# deltabot-heater-bed.net
KiCad netlist of a schematic drawn in EAGLE
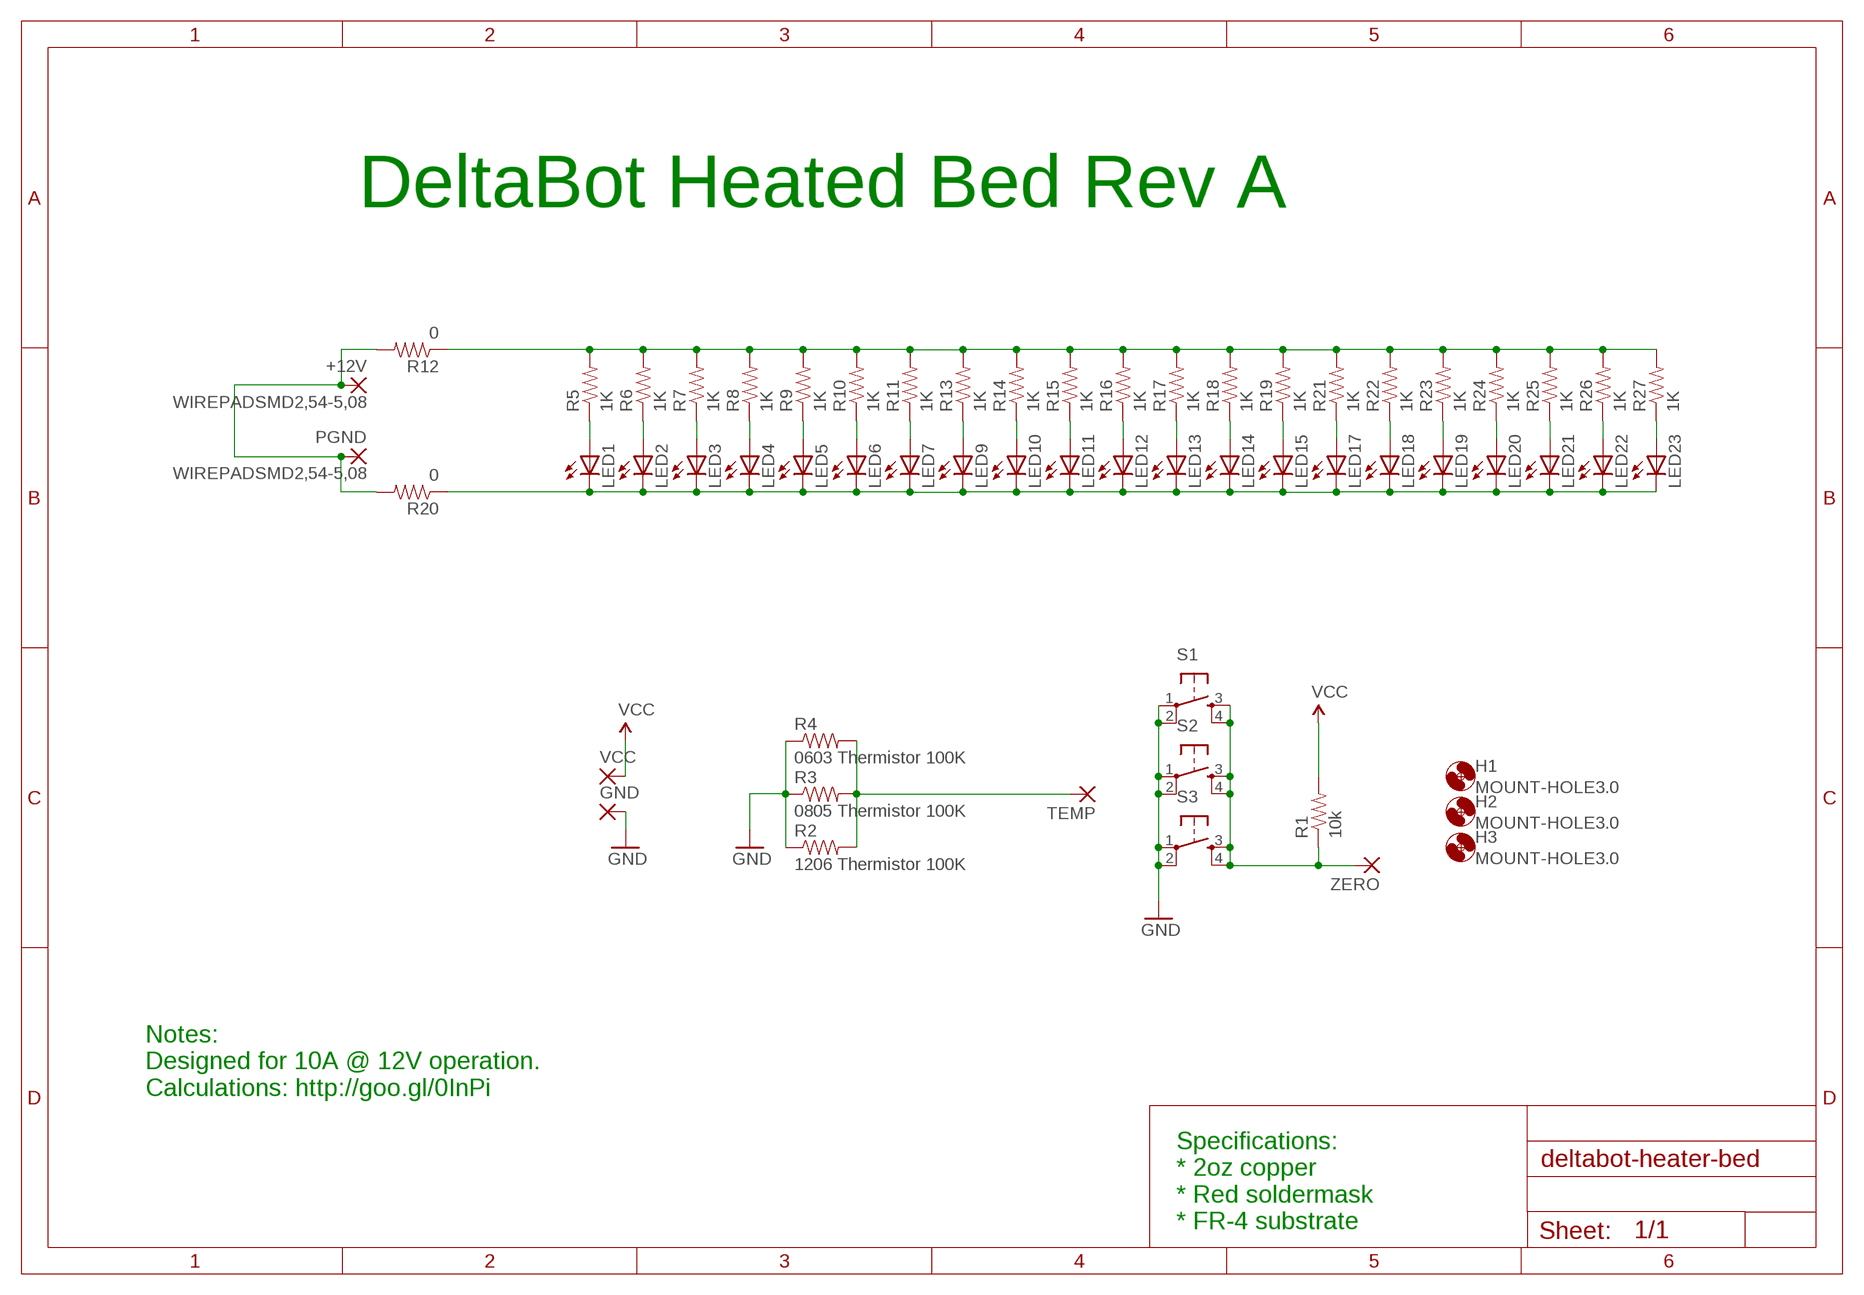
[diagram p0: schematic, sheet 1]

(export (version "E")
  (design (tool "Eeschema 10.0.6"))
  (components
    (comp (ref "+12V")
      (value "WIREPADSMD2,54-5,08")
      (footprint "eagle-import:SMD2,54-5,08")
      (libsource (lib "eagle-import") (part "WIREPADSMD2,54-5,08"))
    )
    (comp (ref "GND")
      (value "SMD2")
      (footprint "eagle-import:SMD1,27-2,54")
      (libsource (lib "eagle-import") (part "SMD2"))
    )
    (comp (ref "H1")
      (value "MOUNT-HOLE3.0")
      (footprint "eagle-import:3,0")
      (libsource (lib "eagle-import") (part "MOUNT-HOLE3.0"))
    )
    (comp (ref "H2")
      (value "MOUNT-HOLE3.0")
      (footprint "eagle-import:3,0")
      (libsource (lib "eagle-import") (part "MOUNT-HOLE3.0"))
    )
    (comp (ref "H3")
      (value "MOUNT-HOLE3.0")
      (footprint "eagle-import:3,0")
      (libsource (lib "eagle-import") (part "MOUNT-HOLE3.0"))
    )
    (comp (ref "LED1")
      (value "LED0805")
      (footprint "eagle-import:0805-LED")
      (libsource (lib "eagle-import") (part "LED0805"))
    )
    (comp (ref "LED2")
      (value "LED0805")
      (footprint "eagle-import:0805-LED")
      (libsource (lib "eagle-import") (part "LED0805"))
    )
    (comp (ref "LED3")
      (value "LED0805")
      (footprint "eagle-import:0805-LED")
      (libsource (lib "eagle-import") (part "LED0805"))
    )
    (comp (ref "LED4")
      (value "LED0805")
      (footprint "eagle-import:0805-LED")
      (libsource (lib "eagle-import") (part "LED0805"))
    )
    (comp (ref "LED5")
      (value "LED0805")
      (footprint "eagle-import:0805-LED")
      (libsource (lib "eagle-import") (part "LED0805"))
    )
    (comp (ref "LED6")
      (value "LED0805")
      (footprint "eagle-import:0805-LED")
      (libsource (lib "eagle-import") (part "LED0805"))
    )
    (comp (ref "LED7")
      (value "LED0805")
      (footprint "eagle-import:0805-LED")
      (libsource (lib "eagle-import") (part "LED0805"))
    )
    (comp (ref "LED9")
      (value "LED0805")
      (footprint "eagle-import:0805-LED")
      (libsource (lib "eagle-import") (part "LED0805"))
    )
    (comp (ref "LED10")
      (value "LED0805")
      (footprint "eagle-import:0805-LED")
      (libsource (lib "eagle-import") (part "LED0805"))
    )
    (comp (ref "LED11")
      (value "LED0805")
      (footprint "eagle-import:0805-LED")
      (libsource (lib "eagle-import") (part "LED0805"))
    )
    (comp (ref "LED12")
      (value "LED0805")
      (footprint "eagle-import:0805-LED")
      (libsource (lib "eagle-import") (part "LED0805"))
    )
    (comp (ref "LED13")
      (value "LED0805")
      (footprint "eagle-import:0805-LED")
      (libsource (lib "eagle-import") (part "LED0805"))
    )
    (comp (ref "LED14")
      (value "LED0805")
      (footprint "eagle-import:0805-LED")
      (libsource (lib "eagle-import") (part "LED0805"))
    )
    (comp (ref "LED15")
      (value "LED0805")
      (footprint "eagle-import:0805-LED")
      (libsource (lib "eagle-import") (part "LED0805"))
    )
    (comp (ref "LED17")
      (value "LED0805")
      (footprint "eagle-import:0805-LED")
      (libsource (lib "eagle-import") (part "LED0805"))
    )
    (comp (ref "LED18")
      (value "LED0805")
      (footprint "eagle-import:0805-LED")
      (libsource (lib "eagle-import") (part "LED0805"))
    )
    (comp (ref "LED19")
      (value "LED0805")
      (footprint "eagle-import:0805-LED")
      (libsource (lib "eagle-import") (part "LED0805"))
    )
    (comp (ref "LED20")
      (value "LED0805")
      (footprint "eagle-import:0805-LED")
      (libsource (lib "eagle-import") (part "LED0805"))
    )
    (comp (ref "LED21")
      (value "LED0805")
      (footprint "eagle-import:0805-LED")
      (libsource (lib "eagle-import") (part "LED0805"))
    )
    (comp (ref "LED22")
      (value "LED0805")
      (footprint "eagle-import:0805-LED")
      (libsource (lib "eagle-import") (part "LED0805"))
    )
    (comp (ref "LED23")
      (value "LED0805")
      (footprint "eagle-import:0805-LED")
      (libsource (lib "eagle-import") (part "LED0805"))
    )
    (comp (ref "PGND")
      (value "WIREPADSMD2,54-5,08")
      (footprint "eagle-import:SMD2,54-5,08")
      (libsource (lib "eagle-import") (part "WIREPADSMD2,54-5,08"))
    )
    (comp (ref "R1")
      (value "10k")
      (footprint "eagle-import:0805-RC")
      (libsource (lib "eagle-import") (part "RESISTOR0805"))
    )
    (comp (ref "R2")
      (value "1206 Thermistor 100K")
      (footprint "eagle-import:1206-RC")
      (libsource (lib "eagle-import") (part "RESISTOR1206"))
    )
    (comp (ref "R3")
      (value "0805 Thermistor 100K")
      (footprint "eagle-import:0805-RC")
      (libsource (lib "eagle-import") (part "RESISTOR0805"))
    )
    (comp (ref "R4")
      (value "0603 Thermistor 100K")
      (footprint "eagle-import:0603-RC")
      (libsource (lib "eagle-import") (part "RESISTOR0603"))
    )
    (comp (ref "R5")
      (value "1K")
      (footprint "eagle-import:0805-RC")
      (libsource (lib "eagle-import") (part "RESISTOR0805"))
    )
    (comp (ref "R6")
      (value "1K")
      (footprint "eagle-import:0805-RC")
      (libsource (lib "eagle-import") (part "RESISTOR0805"))
    )
    (comp (ref "R7")
      (value "1K")
      (footprint "eagle-import:0805-RC")
      (libsource (lib "eagle-import") (part "RESISTOR0805"))
    )
    (comp (ref "R8")
      (value "1K")
      (footprint "eagle-import:0805-RC")
      (libsource (lib "eagle-import") (part "RESISTOR0805"))
    )
    (comp (ref "R9")
      (value "1K")
      (footprint "eagle-import:0805-RC")
      (libsource (lib "eagle-import") (part "RESISTOR0805"))
    )
    (comp (ref "R10")
      (value "1K")
      (footprint "eagle-import:0805-RC")
      (libsource (lib "eagle-import") (part "RESISTOR0805"))
    )
    (comp (ref "R11")
      (value "1K")
      (footprint "eagle-import:0805-RC")
      (libsource (lib "eagle-import") (part "RESISTOR0805"))
    )
    (comp (ref "R12")
      (value "0")
      (footprint "eagle-import:0805-RC")
      (libsource (lib "eagle-import") (part "RESISTOR0805"))
    )
    (comp (ref "R13")
      (value "1K")
      (footprint "eagle-import:0805-RC")
      (libsource (lib "eagle-import") (part "RESISTOR0805"))
    )
    (comp (ref "R14")
      (value "1K")
      (footprint "eagle-import:0805-RC")
      (libsource (lib "eagle-import") (part "RESISTOR0805"))
    )
    (comp (ref "R15")
      (value "1K")
      (footprint "eagle-import:0805-RC")
      (libsource (lib "eagle-import") (part "RESISTOR0805"))
    )
    (comp (ref "R16")
      (value "1K")
      (footprint "eagle-import:0805-RC")
      (libsource (lib "eagle-import") (part "RESISTOR0805"))
    )
    (comp (ref "R17")
      (value "1K")
      (footprint "eagle-import:0805-RC")
      (libsource (lib "eagle-import") (part "RESISTOR0805"))
    )
    (comp (ref "R18")
      (value "1K")
      (footprint "eagle-import:0805-RC")
      (libsource (lib "eagle-import") (part "RESISTOR0805"))
    )
    (comp (ref "R19")
      (value "1K")
      (footprint "eagle-import:0805-RC")
      (libsource (lib "eagle-import") (part "RESISTOR0805"))
    )
    (comp (ref "R20")
      (value "0")
      (footprint "eagle-import:0805-RC")
      (libsource (lib "eagle-import") (part "RESISTOR0805"))
    )
    (comp (ref "R21")
      (value "1K")
      (footprint "eagle-import:0805-RC")
      (libsource (lib "eagle-import") (part "RESISTOR0805"))
    )
    (comp (ref "R22")
      (value "1K")
      (footprint "eagle-import:0805-RC")
      (libsource (lib "eagle-import") (part "RESISTOR0805"))
    )
    (comp (ref "R23")
      (value "1K")
      (footprint "eagle-import:0805-RC")
      (libsource (lib "eagle-import") (part "RESISTOR0805"))
    )
    (comp (ref "R24")
      (value "1K")
      (footprint "eagle-import:0805-RC")
      (libsource (lib "eagle-import") (part "RESISTOR0805"))
    )
    (comp (ref "R25")
      (value "1K")
      (footprint "eagle-import:0805-RC")
      (libsource (lib "eagle-import") (part "RESISTOR0805"))
    )
    (comp (ref "R26")
      (value "1K")
      (footprint "eagle-import:0805-RC")
      (libsource (lib "eagle-import") (part "RESISTOR0805"))
    )
    (comp (ref "R27")
      (value "1K")
      (footprint "eagle-import:0805-RC")
      (libsource (lib "eagle-import") (part "RESISTOR0805"))
    )
    (comp (ref "S1")
      (value "TAC_SWITCHSMD")
      (footprint "eagle-import:TACTILE_SWITCH_SMD")
      (libsource (lib "eagle-import") (part "TAC_SWITCHSMD"))
    )
    (comp (ref "S2")
      (value "TAC_SWITCHSMD")
      (footprint "eagle-import:TACTILE_SWITCH_SMD")
      (libsource (lib "eagle-import") (part "TAC_SWITCHSMD"))
    )
    (comp (ref "S3")
      (value "TAC_SWITCHSMD")
      (footprint "eagle-import:TACTILE_SWITCH_SMD")
      (libsource (lib "eagle-import") (part "TAC_SWITCHSMD"))
    )
    (comp (ref "TEMP")
      (value "SMD2")
      (footprint "eagle-import:SMD1,27-2,54")
      (libsource (lib "eagle-import") (part "SMD2"))
    )
    (comp (ref "VCC")
      (value "SMD2")
      (footprint "eagle-import:SMD1,27-2,54")
      (libsource (lib "eagle-import") (part "SMD2"))
    )
    (comp (ref "ZERO")
      (value "SMD2")
      (footprint "eagle-import:SMD1,27-2,54")
      (libsource (lib "eagle-import") (part "SMD2"))
    )
  )
  (nets
    (net (code "1") (name "GND") (class "Default")
      (node (ref "GND") (pin "1") (pinfunction "P_1") (pintype "passive"))
      (node (ref "R2") (pin "1") (pinfunction "1_1") (pintype "passive"))
      (node (ref "R3") (pin "1") (pinfunction "1_1") (pintype "passive"))
      (node (ref "R4") (pin "1") (pinfunction "1_1") (pintype "passive"))
      (node (ref "S1") (pin "1") (pinfunction "1_1") (pintype "passive"))
      (node (ref "S1") (pin "2") (pinfunction "2_2") (pintype "passive"))
      (node (ref "S2") (pin "1") (pinfunction "1_1") (pintype "passive"))
      (node (ref "S2") (pin "2") (pinfunction "2_2") (pintype "passive"))
      (node (ref "S3") (pin "1") (pinfunction "1_1") (pintype "passive"))
      (node (ref "S3") (pin "2") (pinfunction "2_2") (pintype "passive"))
    )
    (net (code "2") (name "Net-(+12V-P)") (class "Default")
      (node (ref "+12V") (pin "1") (pinfunction "P_1") (pintype "passive"))
      (node (ref "PGND") (pin "1") (pinfunction "P_1") (pintype "passive"))
      (node (ref "R12") (pin "2") (pinfunction "2_2") (pintype "passive"))
      (node (ref "R20") (pin "2") (pinfunction "2_2") (pintype "passive"))
    )
    (net (code "3") (name "Net-(LED1-PadA)") (class "Default")
      (node (ref "LED1") (pin "A") (pinfunction "A_A") (pintype "passive"))
      (node (ref "R5") (pin "1") (pinfunction "1_1") (pintype "passive"))
    )
    (net (code "4") (name "Net-(LED1-PadC)") (class "Default")
      (node (ref "LED1") (pin "C") (pinfunction "C_C") (pintype "passive"))
      (node (ref "LED10") (pin "C") (pinfunction "C_C") (pintype "passive"))
      (node (ref "LED11") (pin "C") (pinfunction "C_C") (pintype "passive"))
      (node (ref "LED12") (pin "C") (pinfunction "C_C") (pintype "passive"))
      (node (ref "LED13") (pin "C") (pinfunction "C_C") (pintype "passive"))
      (node (ref "LED14") (pin "C") (pinfunction "C_C") (pintype "passive"))
      (node (ref "LED15") (pin "C") (pinfunction "C_C") (pintype "passive"))
      (node (ref "LED17") (pin "C") (pinfunction "C_C") (pintype "passive"))
      (node (ref "LED18") (pin "C") (pinfunction "C_C") (pintype "passive"))
      (node (ref "LED19") (pin "C") (pinfunction "C_C") (pintype "passive"))
      (node (ref "LED2") (pin "C") (pinfunction "C_C") (pintype "passive"))
      (node (ref "LED20") (pin "C") (pinfunction "C_C") (pintype "passive"))
      (node (ref "LED21") (pin "C") (pinfunction "C_C") (pintype "passive"))
      (node (ref "LED22") (pin "C") (pinfunction "C_C") (pintype "passive"))
      (node (ref "LED23") (pin "C") (pinfunction "C_C") (pintype "passive"))
      (node (ref "LED3") (pin "C") (pinfunction "C_C") (pintype "passive"))
      (node (ref "LED4") (pin "C") (pinfunction "C_C") (pintype "passive"))
      (node (ref "LED5") (pin "C") (pinfunction "C_C") (pintype "passive"))
      (node (ref "LED6") (pin "C") (pinfunction "C_C") (pintype "passive"))
      (node (ref "LED7") (pin "C") (pinfunction "C_C") (pintype "passive"))
      (node (ref "LED9") (pin "C") (pinfunction "C_C") (pintype "passive"))
      (node (ref "R20") (pin "1") (pinfunction "1_1") (pintype "passive"))
    )
    (net (code "5") (name "Net-(LED2-PadA)") (class "Default")
      (node (ref "LED2") (pin "A") (pinfunction "A_A") (pintype "passive"))
      (node (ref "R6") (pin "1") (pinfunction "1_1") (pintype "passive"))
    )
    (net (code "6") (name "Net-(LED3-PadA)") (class "Default")
      (node (ref "LED3") (pin "A") (pinfunction "A_A") (pintype "passive"))
      (node (ref "R7") (pin "1") (pinfunction "1_1") (pintype "passive"))
    )
    (net (code "7") (name "Net-(LED4-PadA)") (class "Default")
      (node (ref "LED4") (pin "A") (pinfunction "A_A") (pintype "passive"))
      (node (ref "R8") (pin "1") (pinfunction "1_1") (pintype "passive"))
    )
    (net (code "8") (name "Net-(LED5-PadA)") (class "Default")
      (node (ref "LED5") (pin "A") (pinfunction "A_A") (pintype "passive"))
      (node (ref "R9") (pin "1") (pinfunction "1_1") (pintype "passive"))
    )
    (net (code "9") (name "Net-(LED6-PadA)") (class "Default")
      (node (ref "LED6") (pin "A") (pinfunction "A_A") (pintype "passive"))
      (node (ref "R10") (pin "1") (pinfunction "1_1") (pintype "passive"))
    )
    (net (code "10") (name "Net-(LED7-PadA)") (class "Default")
      (node (ref "LED7") (pin "A") (pinfunction "A_A") (pintype "passive"))
      (node (ref "R11") (pin "1") (pinfunction "1_1") (pintype "passive"))
    )
    (net (code "11") (name "Net-(LED9-PadA)") (class "Default")
      (node (ref "LED9") (pin "A") (pinfunction "A_A") (pintype "passive"))
      (node (ref "R13") (pin "1") (pinfunction "1_1") (pintype "passive"))
    )
    (net (code "12") (name "Net-(LED10-PadA)") (class "Default")
      (node (ref "LED10") (pin "A") (pinfunction "A_A") (pintype "passive"))
      (node (ref "R14") (pin "1") (pinfunction "1_1") (pintype "passive"))
    )
    (net (code "13") (name "Net-(LED11-PadA)") (class "Default")
      (node (ref "LED11") (pin "A") (pinfunction "A_A") (pintype "passive"))
      (node (ref "R15") (pin "1") (pinfunction "1_1") (pintype "passive"))
    )
    (net (code "14") (name "Net-(LED12-PadA)") (class "Default")
      (node (ref "LED12") (pin "A") (pinfunction "A_A") (pintype "passive"))
      (node (ref "R16") (pin "1") (pinfunction "1_1") (pintype "passive"))
    )
    (net (code "15") (name "Net-(LED13-PadA)") (class "Default")
      (node (ref "LED13") (pin "A") (pinfunction "A_A") (pintype "passive"))
      (node (ref "R17") (pin "1") (pinfunction "1_1") (pintype "passive"))
    )
    (net (code "16") (name "Net-(LED14-PadA)") (class "Default")
      (node (ref "LED14") (pin "A") (pinfunction "A_A") (pintype "passive"))
      (node (ref "R18") (pin "1") (pinfunction "1_1") (pintype "passive"))
    )
    (net (code "17") (name "Net-(LED15-PadA)") (class "Default")
      (node (ref "LED15") (pin "A") (pinfunction "A_A") (pintype "passive"))
      (node (ref "R19") (pin "1") (pinfunction "1_1") (pintype "passive"))
    )
    (net (code "18") (name "Net-(LED17-PadA)") (class "Default")
      (node (ref "LED17") (pin "A") (pinfunction "A_A") (pintype "passive"))
      (node (ref "R21") (pin "1") (pinfunction "1_1") (pintype "passive"))
    )
    (net (code "19") (name "Net-(LED18-PadA)") (class "Default")
      (node (ref "LED18") (pin "A") (pinfunction "A_A") (pintype "passive"))
      (node (ref "R22") (pin "1") (pinfunction "1_1") (pintype "passive"))
    )
    (net (code "20") (name "Net-(LED19-PadA)") (class "Default")
      (node (ref "LED19") (pin "A") (pinfunction "A_A") (pintype "passive"))
      (node (ref "R23") (pin "1") (pinfunction "1_1") (pintype "passive"))
    )
    (net (code "21") (name "Net-(LED20-PadA)") (class "Default")
      (node (ref "LED20") (pin "A") (pinfunction "A_A") (pintype "passive"))
      (node (ref "R24") (pin "1") (pinfunction "1_1") (pintype "passive"))
    )
    (net (code "22") (name "Net-(LED21-PadA)") (class "Default")
      (node (ref "LED21") (pin "A") (pinfunction "A_A") (pintype "passive"))
      (node (ref "R25") (pin "1") (pinfunction "1_1") (pintype "passive"))
    )
    (net (code "23") (name "Net-(LED22-PadA)") (class "Default")
      (node (ref "LED22") (pin "A") (pinfunction "A_A") (pintype "passive"))
      (node (ref "R26") (pin "1") (pinfunction "1_1") (pintype "passive"))
    )
    (net (code "24") (name "Net-(LED23-PadA)") (class "Default")
      (node (ref "LED23") (pin "A") (pinfunction "A_A") (pintype "passive"))
      (node (ref "R27") (pin "1") (pinfunction "1_1") (pintype "passive"))
    )
    (net (code "25") (name "Net-(R2-2)") (class "Default")
      (node (ref "R2") (pin "2.") (pinfunction "2_2.") (pintype "passive"))
      (node (ref "R3") (pin "2") (pinfunction "2_2") (pintype "passive"))
      (node (ref "R4") (pin "2") (pinfunction "2_2") (pintype "passive"))
      (node (ref "TEMP") (pin "1") (pinfunction "P_1") (pintype "passive"))
    )
    (net (code "26") (name "Net-(R10-Pad2)") (class "Default")
      (node (ref "R10") (pin "2") (pinfunction "2_2") (pintype "passive"))
      (node (ref "R11") (pin "2") (pinfunction "2_2") (pintype "passive"))
      (node (ref "R12") (pin "1") (pinfunction "1_1") (pintype "passive"))
      (node (ref "R13") (pin "2") (pinfunction "2_2") (pintype "passive"))
      (node (ref "R14") (pin "2") (pinfunction "2_2") (pintype "passive"))
      (node (ref "R15") (pin "2") (pinfunction "2_2") (pintype "passive"))
      (node (ref "R16") (pin "2") (pinfunction "2_2") (pintype "passive"))
      (node (ref "R17") (pin "2") (pinfunction "2_2") (pintype "passive"))
      (node (ref "R18") (pin "2") (pinfunction "2_2") (pintype "passive"))
      (node (ref "R19") (pin "2") (pinfunction "2_2") (pintype "passive"))
      (node (ref "R21") (pin "2") (pinfunction "2_2") (pintype "passive"))
      (node (ref "R22") (pin "2") (pinfunction "2_2") (pintype "passive"))
      (node (ref "R23") (pin "2") (pinfunction "2_2") (pintype "passive"))
      (node (ref "R24") (pin "2") (pinfunction "2_2") (pintype "passive"))
      (node (ref "R25") (pin "2") (pinfunction "2_2") (pintype "passive"))
      (node (ref "R26") (pin "2") (pinfunction "2_2") (pintype "passive"))
      (node (ref "R27") (pin "2") (pinfunction "2_2") (pintype "passive"))
      (node (ref "R5") (pin "2") (pinfunction "2_2") (pintype "passive"))
      (node (ref "R6") (pin "2") (pinfunction "2_2") (pintype "passive"))
      (node (ref "R7") (pin "2") (pinfunction "2_2") (pintype "passive"))
      (node (ref "R8") (pin "2") (pinfunction "2_2") (pintype "passive"))
      (node (ref "R9") (pin "2") (pinfunction "2_2") (pintype "passive"))
    )
    (net (code "27") (name "Net-(ZERO-P)") (class "Default")
      (node (ref "R1") (pin "1") (pinfunction "1_1") (pintype "passive"))
      (node (ref "S1") (pin "3") (pinfunction "3_3") (pintype "passive"))
      (node (ref "S1") (pin "4") (pinfunction "4_4") (pintype "passive"))
      (node (ref "S2") (pin "3") (pinfunction "3_3") (pintype "passive"))
      (node (ref "S2") (pin "4") (pinfunction "4_4") (pintype "passive"))
      (node (ref "S3") (pin "3") (pinfunction "3_3") (pintype "passive"))
      (node (ref "S3") (pin "4") (pinfunction "4_4") (pintype "passive"))
      (node (ref "ZERO") (pin "1") (pinfunction "P_1") (pintype "passive"))
    )
    (net (code "28") (name "VCC") (class "Default")
      (node (ref "R1") (pin "2") (pinfunction "2_2") (pintype "passive"))
      (node (ref "VCC") (pin "1") (pinfunction "P_1") (pintype "passive"))
    )
  )
)
